# PCB-ARD-DUEBOS_2016.net
KiCad netlist of a schematic drawn in EAGLE
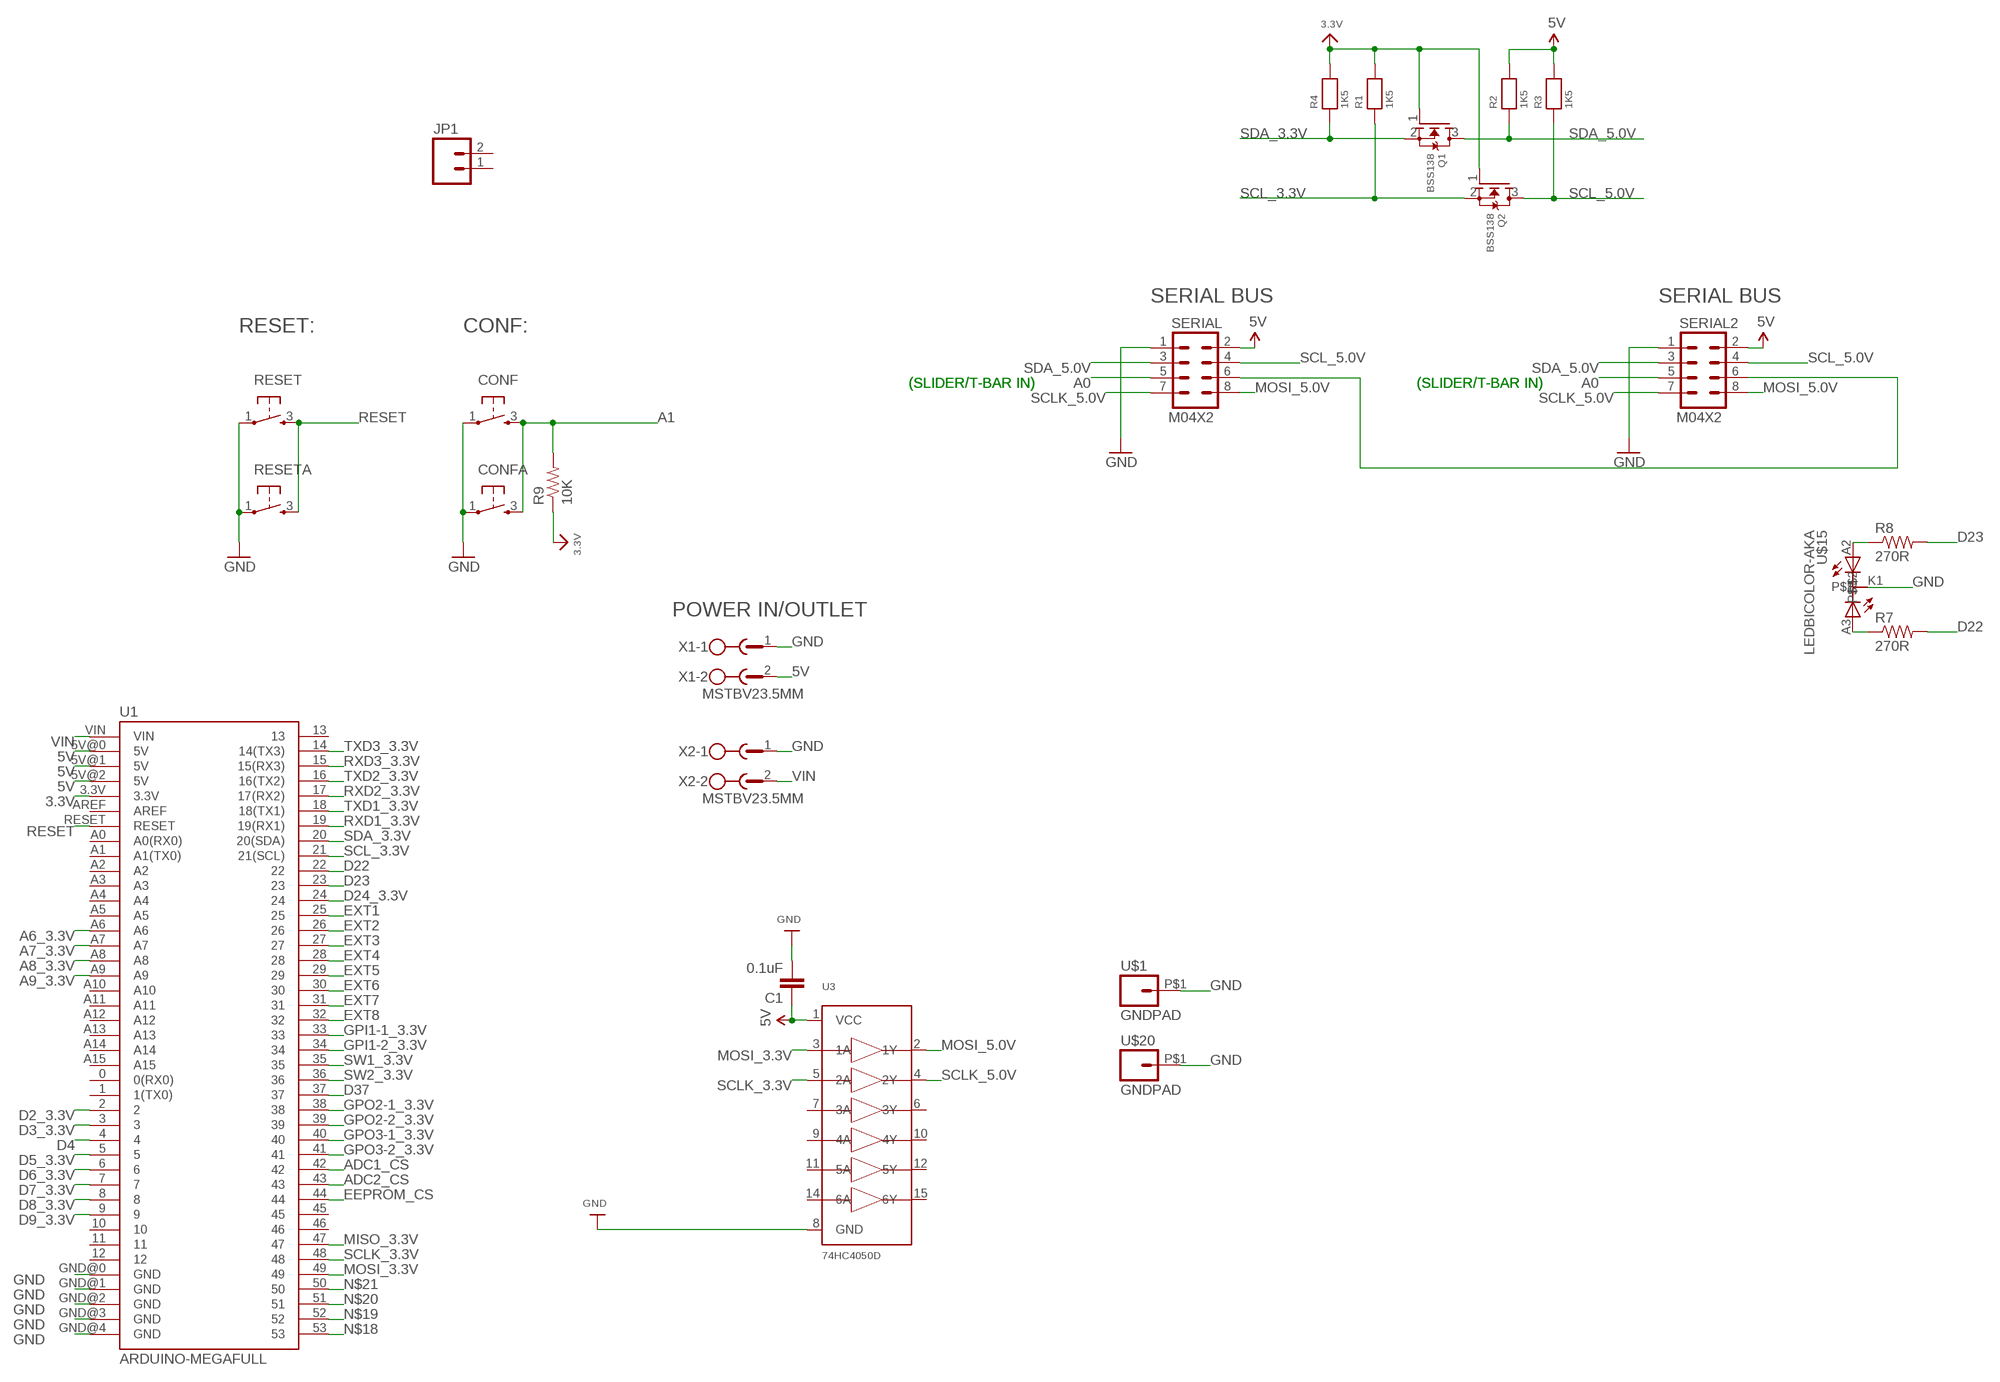
[diagram p0: schematic, sheet 1]

(export (version "E")
  (design (tool "Eeschema 10.0.6"))
  (components
    (comp (ref "C1")
      (value "0.1uF")
      (footprint "eagle-import:0603-CAP")
      (libsource (lib "eagle-import") (part "CAP0603-CAP"))
    )
    (comp (ref "CONF")
      (value "TAC_SWITCH")
      (footprint "eagle-import:PUSHBUTTON")
      (libsource (lib "eagle-import") (part "TAC_SWITCH"))
    )
    (comp (ref "CONFA")
      (value "TAC_SWITCH")
      (footprint "eagle-import:PUSHBUTTON")
      (libsource (lib "eagle-import") (part "TAC_SWITCH"))
    )
    (comp (ref "JP1")
      (value "M02PTH")
      (footprint "eagle-import:1X02")
      (libsource (lib "eagle-import") (part "M02PTH"))
    )
    (comp (ref "Q1")
      (value "BSS138")
      (footprint "eagle-import:SOT23-R")
      (libsource (lib "eagle-import") (part "MOSFET-NREFLOW"))
    )
    (comp (ref "Q2")
      (value "BSS138")
      (footprint "eagle-import:SOT23-R")
      (libsource (lib "eagle-import") (part "MOSFET-NREFLOW"))
    )
    (comp (ref "R1")
      (value "1K5")
      (footprint "eagle-import:0603")
      (libsource (lib "eagle-import") (part "RESISTOR0603"))
    )
    (comp (ref "R2")
      (value "1K5")
      (footprint "eagle-import:0603")
      (libsource (lib "eagle-import") (part "RESISTOR0603"))
    )
    (comp (ref "R3")
      (value "1K5")
      (footprint "eagle-import:0603")
      (libsource (lib "eagle-import") (part "RESISTOR0603"))
    )
    (comp (ref "R4")
      (value "1K5")
      (footprint "eagle-import:0603")
      (libsource (lib "eagle-import") (part "RESISTOR0603"))
    )
    (comp (ref "R7")
      (value "270R")
      (footprint "eagle-import:0603-RES")
      (libsource (lib "eagle-import") (part "RESISTOR0603-RES"))
    )
    (comp (ref "R8")
      (value "270R")
      (footprint "eagle-import:0603-RES")
      (libsource (lib "eagle-import") (part "RESISTOR0603-RES"))
    )
    (comp (ref "R9")
      (value "10K")
      (footprint "eagle-import:0603-RES")
      (libsource (lib "eagle-import") (part "RESISTOR0603-RES"))
    )
    (comp (ref "RESET")
      (value "TAC_SWITCH")
      (footprint "eagle-import:PUSHBUTTON")
      (libsource (lib "eagle-import") (part "TAC_SWITCH"))
    )
    (comp (ref "RESETA")
      (value "TAC_SWITCH")
      (footprint "eagle-import:PUSHBUTTON")
      (libsource (lib "eagle-import") (part "TAC_SWITCH"))
    )
    (comp (ref "SERIAL")
      (value "M04X2")
      (footprint "eagle-import:2X4")
      (libsource (lib "eagle-import") (part "M04X2"))
    )
    (comp (ref "SERIAL2")
      (value "M04X2")
      (footprint "eagle-import:2X4")
      (libsource (lib "eagle-import") (part "M04X2"))
    )
    (comp (ref "U$1")
      (value "GNDPAD")
      (footprint "eagle-import:3.2MMPAD")
      (libsource (lib "eagle-import") (part "GNDPAD"))
    )
    (comp (ref "U$15")
      (value "LEDBICOLOR-AKA")
      (footprint "eagle-import:LED5MM-BICOLOR")
      (libsource (lib "eagle-import") (part "LEDBICOLOR-AKA"))
    )
    (comp (ref "U$20")
      (value "GNDPAD")
      (footprint "eagle-import:3.2MMPAD")
      (libsource (lib "eagle-import") (part "GNDPAD"))
    )
    (comp (ref "U1")
      (value "ARDUINO-MEGAFULL")
      (footprint "eagle-import:ARDUINO_MEGA")
      (libsource (lib "eagle-import") (part "ARDUINO-MEGAFULL"))
    )
    (comp (ref "U3")
      (value "74HC4050D")
      (footprint "eagle-import:TSSOP16")
      (libsource (lib "eagle-import") (part "74HC4050DTSSOP16"))
    )
    (comp (ref "X1")
      (value "MSTBV23.5MM")
      (footprint "eagle-import:MSTBV2-3.5")
      (libsource (lib "eagle-import") (part "MSTBV23.5MM"))
    )
    (comp (ref "X2")
      (value "MSTBV23.5MM")
      (footprint "eagle-import:MSTBV2-3.5")
      (libsource (lib "eagle-import") (part "MSTBV23.5MM"))
    )
  )
  (nets
    (net (code "1") (name "/A0") (class "Default")
      (node (ref "SERIAL") (pin "5") (pinfunction "5_5") (pintype "passive"))
      (node (ref "SERIAL2") (pin "5") (pinfunction "5_5") (pintype "passive"))
    )
    (net (code "2") (name "/A1") (class "Default")
      (node (ref "CONF") (pin "3") (pinfunction "3_3") (pintype "passive"))
      (node (ref "CONFA") (pin "3") (pinfunction "3_3") (pintype "passive"))
      (node (ref "R9") (pin "2") (pinfunction "2_2") (pintype "passive"))
    )
    (net (code "3") (name "/A6_3.3V") (class "Default")
      (node (ref "U1") (pin "A6") (pinfunction "A6_A6") (pintype "bidirectional"))
    )
    (net (code "4") (name "/A7_3.3V") (class "Default")
      (node (ref "U1") (pin "A7") (pinfunction "A7_A7") (pintype "bidirectional"))
    )
    (net (code "5") (name "/A8_3.3V") (class "Default")
      (node (ref "U1") (pin "A8") (pinfunction "A8_A8") (pintype "bidirectional"))
    )
    (net (code "6") (name "/A9_3.3V") (class "Default")
      (node (ref "U1") (pin "A9") (pinfunction "A9_A9") (pintype "bidirectional"))
    )
    (net (code "7") (name "/ADC1_CS") (class "Default")
      (node (ref "U1") (pin "42") (pinfunction "42_42") (pintype "bidirectional"))
    )
    (net (code "8") (name "/ADC2_CS") (class "Default")
      (node (ref "U1") (pin "43") (pinfunction "43_43") (pintype "bidirectional"))
    )
    (net (code "9") (name "/D2_3.3V") (class "Default")
      (node (ref "U1") (pin "2") (pinfunction "2_2") (pintype "bidirectional"))
    )
    (net (code "10") (name "/D3_3.3V") (class "Default")
      (node (ref "U1") (pin "3") (pinfunction "3_3") (pintype "bidirectional"))
    )
    (net (code "11") (name "/D4") (class "Default")
      (node (ref "U1") (pin "4") (pinfunction "4_4") (pintype "bidirectional"))
    )
    (net (code "12") (name "/D5_3.3V") (class "Default")
      (node (ref "U1") (pin "5") (pinfunction "5_5") (pintype "bidirectional"))
    )
    (net (code "13") (name "/D6_3.3V") (class "Default")
      (node (ref "U1") (pin "6") (pinfunction "6_6") (pintype "bidirectional"))
    )
    (net (code "14") (name "/D7_3.3V") (class "Default")
      (node (ref "U1") (pin "7") (pinfunction "7_7") (pintype "bidirectional"))
    )
    (net (code "15") (name "/D8_3.3V") (class "Default")
      (node (ref "U1") (pin "8") (pinfunction "8_8") (pintype "bidirectional"))
    )
    (net (code "16") (name "/D9_3.3V") (class "Default")
      (node (ref "U1") (pin "9") (pinfunction "9_9") (pintype "bidirectional"))
    )
    (net (code "17") (name "/D22") (class "Default")
      (node (ref "R7") (pin "2") (pinfunction "2_2") (pintype "passive"))
      (node (ref "U1") (pin "22") (pinfunction "22_22") (pintype "bidirectional"))
    )
    (net (code "18") (name "/D23") (class "Default")
      (node (ref "R8") (pin "2") (pinfunction "2_2") (pintype "passive"))
      (node (ref "U1") (pin "23") (pinfunction "23_23") (pintype "bidirectional"))
    )
    (net (code "19") (name "/D24_3.3V") (class "Default")
      (node (ref "U1") (pin "24") (pinfunction "24_24") (pintype "bidirectional"))
    )
    (net (code "20") (name "/D37") (class "Default")
      (node (ref "U1") (pin "37") (pinfunction "37_37") (pintype "bidirectional"))
    )
    (net (code "21") (name "/EEPROM_CS") (class "Default")
      (node (ref "U1") (pin "44") (pinfunction "44_44") (pintype "bidirectional"))
    )
    (net (code "22") (name "/EXT1") (class "Default")
      (node (ref "U1") (pin "25") (pinfunction "25_25") (pintype "bidirectional"))
    )
    (net (code "23") (name "/EXT2") (class "Default")
      (node (ref "U1") (pin "26") (pinfunction "26_26") (pintype "bidirectional"))
    )
    (net (code "24") (name "/EXT3") (class "Default")
      (node (ref "U1") (pin "27") (pinfunction "27_27") (pintype "bidirectional"))
    )
    (net (code "25") (name "/EXT4") (class "Default")
      (node (ref "U1") (pin "28") (pinfunction "28_28") (pintype "bidirectional"))
    )
    (net (code "26") (name "/EXT5") (class "Default")
      (node (ref "U1") (pin "29") (pinfunction "29_29") (pintype "bidirectional"))
    )
    (net (code "27") (name "/EXT6") (class "Default")
      (node (ref "U1") (pin "30") (pinfunction "30_30") (pintype "bidirectional"))
    )
    (net (code "28") (name "/EXT7") (class "Default")
      (node (ref "U1") (pin "31") (pinfunction "31_31") (pintype "bidirectional"))
    )
    (net (code "29") (name "/EXT8") (class "Default")
      (node (ref "U1") (pin "32") (pinfunction "32_32") (pintype "bidirectional"))
    )
    (net (code "30") (name "/GPI1-1_3.3V") (class "Default")
      (node (ref "U1") (pin "33") (pinfunction "33_33") (pintype "bidirectional"))
    )
    (net (code "31") (name "/GPI1-2_3.3V") (class "Default")
      (node (ref "U1") (pin "34") (pinfunction "34_34") (pintype "bidirectional"))
    )
    (net (code "32") (name "/GPO2-1_3.3V") (class "Default")
      (node (ref "U1") (pin "38") (pinfunction "38_38") (pintype "bidirectional"))
    )
    (net (code "33") (name "/GPO2-2_3.3V") (class "Default")
      (node (ref "U1") (pin "39") (pinfunction "39_39") (pintype "bidirectional"))
    )
    (net (code "34") (name "/GPO3-1_3.3V") (class "Default")
      (node (ref "U1") (pin "40") (pinfunction "40_40") (pintype "bidirectional"))
    )
    (net (code "35") (name "/GPO3-2_3.3V") (class "Default")
      (node (ref "U1") (pin "41") (pinfunction "41_41") (pintype "bidirectional"))
    )
    (net (code "36") (name "/MISO_3.3V") (class "Default")
      (node (ref "U1") (pin "47") (pinfunction "47_47") (pintype "bidirectional"))
    )
    (net (code "37") (name "/MOSI_3.3V") (class "Default")
      (node (ref "U1") (pin "49") (pinfunction "49_49") (pintype "bidirectional"))
      (node (ref "U3") (pin "3") (pinfunction "1A_3") (pintype "bidirectional"))
    )
    (net (code "38") (name "/MOSI_5.0V") (class "Default")
      (node (ref "SERIAL") (pin "8") (pinfunction "8_8") (pintype "passive"))
      (node (ref "SERIAL2") (pin "8") (pinfunction "8_8") (pintype "passive"))
      (node (ref "U3") (pin "2") (pinfunction "1Y_2") (pintype "bidirectional"))
    )
    (net (code "39") (name "/N$18") (class "Default")
      (node (ref "U1") (pin "53") (pinfunction "53_53") (pintype "bidirectional"))
    )
    (net (code "40") (name "/N$19") (class "Default")
      (node (ref "U1") (pin "52") (pinfunction "52_52") (pintype "bidirectional"))
    )
    (net (code "41") (name "/N$20") (class "Default")
      (node (ref "U1") (pin "51") (pinfunction "51_51") (pintype "bidirectional"))
    )
    (net (code "42") (name "/N$21") (class "Default")
      (node (ref "U1") (pin "50") (pinfunction "50_50") (pintype "bidirectional"))
    )
    (net (code "43") (name "/RESET") (class "Default")
      (node (ref "RESET") (pin "3") (pinfunction "3_3") (pintype "passive"))
      (node (ref "RESETA") (pin "3") (pinfunction "3_3") (pintype "passive"))
      (node (ref "U1") (pin "RESET") (pinfunction "RESET_RESET") (pintype "bidirectional"))
    )
    (net (code "44") (name "/RXD1_3.3V") (class "Default")
      (node (ref "U1") (pin "19") (pinfunction "19(RX1)_19") (pintype "bidirectional"))
    )
    (net (code "45") (name "/RXD2_3.3V") (class "Default")
      (node (ref "U1") (pin "17") (pinfunction "17(RX2)_17") (pintype "bidirectional"))
    )
    (net (code "46") (name "/RXD3_3.3V") (class "Default")
      (node (ref "U1") (pin "15") (pinfunction "15(RX3)_15") (pintype "bidirectional"))
    )
    (net (code "47") (name "/SCLK_3.3V") (class "Default")
      (node (ref "U1") (pin "48") (pinfunction "48_48") (pintype "bidirectional"))
      (node (ref "U3") (pin "5") (pinfunction "2A_5") (pintype "bidirectional"))
    )
    (net (code "48") (name "/SCLK_5.0V") (class "Default")
      (node (ref "SERIAL") (pin "7") (pinfunction "7_7") (pintype "passive"))
      (node (ref "SERIAL2") (pin "7") (pinfunction "7_7") (pintype "passive"))
      (node (ref "U3") (pin "4") (pinfunction "2Y_4") (pintype "bidirectional"))
    )
    (net (code "49") (name "/SCL_3.3V") (class "Default")
      (node (ref "Q2") (pin "2") (pinfunction "S_2") (pintype "bidirectional"))
      (node (ref "R1") (pin "1") (pinfunction "1_1") (pintype "passive"))
      (node (ref "U1") (pin "21") (pinfunction "21(SCL)_21") (pintype "bidirectional"))
    )
    (net (code "50") (name "/SCL_5.0V") (class "Default")
      (node (ref "Q2") (pin "3") (pinfunction "D_3") (pintype "bidirectional"))
      (node (ref "R3") (pin "1") (pinfunction "1_1") (pintype "passive"))
      (node (ref "SERIAL") (pin "4") (pinfunction "4_4") (pintype "passive"))
      (node (ref "SERIAL2") (pin "4") (pinfunction "4_4") (pintype "passive"))
    )
    (net (code "51") (name "/SDA_3.3V") (class "Default")
      (node (ref "Q1") (pin "2") (pinfunction "S_2") (pintype "bidirectional"))
      (node (ref "R4") (pin "1") (pinfunction "1_1") (pintype "passive"))
      (node (ref "U1") (pin "20") (pinfunction "20(SDA)_20") (pintype "bidirectional"))
    )
    (net (code "52") (name "/SDA_5.0V") (class "Default")
      (node (ref "Q1") (pin "3") (pinfunction "D_3") (pintype "bidirectional"))
      (node (ref "R2") (pin "1") (pinfunction "1_1") (pintype "passive"))
      (node (ref "SERIAL") (pin "3") (pinfunction "3_3") (pintype "passive"))
      (node (ref "SERIAL2") (pin "3") (pinfunction "3_3") (pintype "passive"))
    )
    (net (code "53") (name "/SW1_3.3V") (class "Default")
      (node (ref "U1") (pin "35") (pinfunction "35_35") (pintype "bidirectional"))
    )
    (net (code "54") (name "/SW2_3.3V") (class "Default")
      (node (ref "U1") (pin "36") (pinfunction "36_36") (pintype "bidirectional"))
    )
    (net (code "55") (name "/TXD1_3.3V") (class "Default")
      (node (ref "U1") (pin "18") (pinfunction "18(TX1)_18") (pintype "bidirectional"))
    )
    (net (code "56") (name "/TXD2_3.3V") (class "Default")
      (node (ref "U1") (pin "16") (pinfunction "16(TX2)_16") (pintype "bidirectional"))
    )
    (net (code "57") (name "/TXD3_3.3V") (class "Default")
      (node (ref "U1") (pin "14") (pinfunction "14(TX3)_14") (pintype "bidirectional"))
    )
    (net (code "58") (name "/VIN") (class "Default")
      (node (ref "U1") (pin "VIN") (pinfunction "VIN_VIN") (pintype "bidirectional"))
      (node (ref "X2") (pin "2") (pinfunction "1_2") (pintype "passive"))
    )
    (net (code "59") (name "3.3V") (class "Default")
      (node (ref "Q1") (pin "1") (pinfunction "G_1") (pintype "bidirectional"))
      (node (ref "Q2") (pin "1") (pinfunction "G_1") (pintype "bidirectional"))
      (node (ref "R1") (pin "2") (pinfunction "2_2") (pintype "passive"))
      (node (ref "R4") (pin "2") (pinfunction "2_2") (pintype "passive"))
      (node (ref "R9") (pin "1") (pinfunction "1_1") (pintype "passive"))
      (node (ref "U1") (pin "3.3V") (pinfunction "3.3V_3.3V") (pintype "bidirectional"))
    )
    (net (code "60") (name "5V") (class "Default")
      (node (ref "C1") (pin "1") (pinfunction "1_1") (pintype "passive"))
      (node (ref "R2") (pin "2") (pinfunction "2_2") (pintype "passive"))
      (node (ref "R3") (pin "2") (pinfunction "2_2") (pintype "passive"))
      (node (ref "SERIAL") (pin "2") (pinfunction "2_2") (pintype "passive"))
      (node (ref "SERIAL2") (pin "2") (pinfunction "2_2") (pintype "passive"))
      (node (ref "U1") (pin "5V@0") (pinfunction "5V_5V@0") (pintype "bidirectional"))
      (node (ref "U1") (pin "5V@1") (pinfunction "5V_5V@1") (pintype "bidirectional"))
      (node (ref "U1") (pin "5V@2") (pinfunction "5V_5V@2") (pintype "bidirectional"))
      (node (ref "U3") (pin "1") (pinfunction "VCC_1") (pintype "bidirectional"))
      (node (ref "X1") (pin "2") (pinfunction "1_2") (pintype "passive"))
    )
    (net (code "61") (name "GND") (class "Default")
      (node (ref "C1") (pin "2") (pinfunction "2_2") (pintype "passive"))
      (node (ref "CONF") (pin "1") (pinfunction "1_1") (pintype "passive"))
      (node (ref "CONFA") (pin "1") (pinfunction "1_1") (pintype "passive"))
      (node (ref "RESET") (pin "1") (pinfunction "1_1") (pintype "passive"))
      (node (ref "RESETA") (pin "1") (pinfunction "1_1") (pintype "passive"))
      (node (ref "SERIAL") (pin "1") (pinfunction "1_1") (pintype "passive"))
      (node (ref "SERIAL2") (pin "1") (pinfunction "1_1") (pintype "passive"))
      (node (ref "U$1") (pin "P$1") (pinfunction "1_P$1") (pintype "passive"))
      (node (ref "U$15") (pin "K1") (pinfunction "P$1_K1") (pintype "bidirectional"))
      (node (ref "U$20") (pin "P$1") (pinfunction "1_P$1") (pintype "passive"))
      (node (ref "U1") (pin "GND@0") (pinfunction "GND_GND@0") (pintype "bidirectional"))
      (node (ref "U1") (pin "GND@1") (pinfunction "GND_GND@1") (pintype "bidirectional"))
      (node (ref "U1") (pin "GND@2") (pinfunction "GND_GND@2") (pintype "bidirectional"))
      (node (ref "U1") (pin "GND@3") (pinfunction "GND_GND@3") (pintype "bidirectional"))
      (node (ref "U1") (pin "GND@4") (pinfunction "GND_GND@4") (pintype "bidirectional"))
      (node (ref "U3") (pin "8") (pinfunction "GND_8") (pintype "bidirectional"))
      (node (ref "X1") (pin "1") (pinfunction "1_1") (pintype "passive"))
      (node (ref "X2") (pin "1") (pinfunction "1_1") (pintype "passive"))
    )
    (net (code "62") (name "Net-(SERIAL-Pad6)") (class "Default")
      (node (ref "SERIAL") (pin "6") (pinfunction "6_6") (pintype "passive"))
      (node (ref "SERIAL2") (pin "6") (pinfunction "6_6") (pintype "passive"))
    )
    (net (code "63") (name "Net-(U$15-P$2)") (class "Default")
      (node (ref "R8") (pin "1") (pinfunction "1_1") (pintype "passive"))
      (node (ref "U$15") (pin "A2") (pinfunction "P$2_A2") (pintype "bidirectional"))
    )
    (net (code "64") (name "Net-(U$15-P$3)") (class "Default")
      (node (ref "R7") (pin "1") (pinfunction "1_1") (pintype "passive"))
      (node (ref "U$15") (pin "A3") (pinfunction "P$3_A3") (pintype "bidirectional"))
    )
    (net (code "65") (name "unconnected-(JP1-Pad1)") (class "Default")
      (node (ref "JP1") (pin "1") (pinfunction "1_1") (pintype "passive"))
    )
    (net (code "66") (name "unconnected-(JP1-Pad2)") (class "Default")
      (node (ref "JP1") (pin "2") (pinfunction "2_2") (pintype "passive"))
    )
    (net (code "67") (name "unconnected-(U1-0(RX0)-Pad0)") (class "Default")
      (node (ref "U1") (pin "0") (pinfunction "0(RX0)_0") (pintype "bidirectional"))
    )
    (net (code "68") (name "unconnected-(U1-1(TX0)-Pad1)") (class "Default")
      (node (ref "U1") (pin "1") (pinfunction "1(TX0)_1") (pintype "bidirectional"))
    )
    (net (code "69") (name "unconnected-(U1-A0(RX0)-PadA0)") (class "Default")
      (node (ref "U1") (pin "A0") (pinfunction "A0(RX0)_A0") (pintype "bidirectional"))
    )
    (net (code "70") (name "unconnected-(U1-A1(TX0)-PadA1)") (class "Default")
      (node (ref "U1") (pin "A1") (pinfunction "A1(TX0)_A1") (pintype "bidirectional"))
    )
    (net (code "71") (name "unconnected-(U1-Pad10)") (class "Default")
      (node (ref "U1") (pin "10") (pinfunction "10_10") (pintype "bidirectional"))
    )
    (net (code "72") (name "unconnected-(U1-Pad11)") (class "Default")
      (node (ref "U1") (pin "11") (pinfunction "11_11") (pintype "bidirectional"))
    )
    (net (code "73") (name "unconnected-(U1-Pad12)") (class "Default")
      (node (ref "U1") (pin "12") (pinfunction "12_12") (pintype "bidirectional"))
    )
    (net (code "74") (name "unconnected-(U1-Pad13)") (class "Default")
      (node (ref "U1") (pin "13") (pinfunction "13_13") (pintype "bidirectional"))
    )
    (net (code "75") (name "unconnected-(U1-Pad45)") (class "Default")
      (node (ref "U1") (pin "45") (pinfunction "45_45") (pintype "bidirectional"))
    )
    (net (code "76") (name "unconnected-(U1-Pad46)") (class "Default")
      (node (ref "U1") (pin "46") (pinfunction "46_46") (pintype "bidirectional"))
    )
    (net (code "77") (name "unconnected-(U1-PadA2)") (class "Default")
      (node (ref "U1") (pin "A2") (pinfunction "A2_A2") (pintype "bidirectional"))
    )
    (net (code "78") (name "unconnected-(U1-PadA3)") (class "Default")
      (node (ref "U1") (pin "A3") (pinfunction "A3_A3") (pintype "bidirectional"))
    )
    (net (code "79") (name "unconnected-(U1-PadA4)") (class "Default")
      (node (ref "U1") (pin "A4") (pinfunction "A4_A4") (pintype "bidirectional"))
    )
    (net (code "80") (name "unconnected-(U1-PadA5)") (class "Default")
      (node (ref "U1") (pin "A5") (pinfunction "A5_A5") (pintype "bidirectional"))
    )
    (net (code "81") (name "unconnected-(U1-PadA10)") (class "Default")
      (node (ref "U1") (pin "A10") (pinfunction "A10_A10") (pintype "bidirectional"))
    )
    (net (code "82") (name "unconnected-(U1-PadA11)") (class "Default")
      (node (ref "U1") (pin "A11") (pinfunction "A11_A11") (pintype "bidirectional"))
    )
    (net (code "83") (name "unconnected-(U1-PadA12)") (class "Default")
      (node (ref "U1") (pin "A12") (pinfunction "A12_A12") (pintype "bidirectional"))
    )
    (net (code "84") (name "unconnected-(U1-PadA13)") (class "Default")
      (node (ref "U1") (pin "A13") (pinfunction "A13_A13") (pintype "bidirectional"))
    )
    (net (code "85") (name "unconnected-(U1-PadA14)") (class "Default")
      (node (ref "U1") (pin "A14") (pinfunction "A14_A14") (pintype "bidirectional"))
    )
    (net (code "86") (name "unconnected-(U1-PadA15)") (class "Default")
      (node (ref "U1") (pin "A15") (pinfunction "A15_A15") (pintype "bidirectional"))
    )
    (net (code "87") (name "unconnected-(U1-PadAREF)") (class "Default")
      (node (ref "U1") (pin "AREF") (pinfunction "AREF_AREF") (pintype "bidirectional"))
    )
    (net (code "88") (name "unconnected-(U3-3A-Pad7)") (class "Default")
      (node (ref "U3") (pin "7") (pinfunction "3A_7") (pintype "bidirectional"))
    )
    (net (code "89") (name "unconnected-(U3-3Y-Pad6)") (class "Default")
      (node (ref "U3") (pin "6") (pinfunction "3Y_6") (pintype "bidirectional"))
    )
    (net (code "90") (name "unconnected-(U3-4A-Pad9)") (class "Default")
      (node (ref "U3") (pin "9") (pinfunction "4A_9") (pintype "bidirectional"))
    )
    (net (code "91") (name "unconnected-(U3-4Y-Pad10)") (class "Default")
      (node (ref "U3") (pin "10") (pinfunction "4Y_10") (pintype "bidirectional"))
    )
    (net (code "92") (name "unconnected-(U3-5A-Pad11)") (class "Default")
      (node (ref "U3") (pin "11") (pinfunction "5A_11") (pintype "bidirectional"))
    )
    (net (code "93") (name "unconnected-(U3-5Y-Pad12)") (class "Default")
      (node (ref "U3") (pin "12") (pinfunction "5Y_12") (pintype "bidirectional"))
    )
    (net (code "94") (name "unconnected-(U3-6A-Pad14)") (class "Default")
      (node (ref "U3") (pin "14") (pinfunction "6A_14") (pintype "bidirectional"))
    )
    (net (code "95") (name "unconnected-(U3-6Y-Pad15)") (class "Default")
      (node (ref "U3") (pin "15") (pinfunction "6Y_15") (pintype "bidirectional"))
    )
  )
)
